# Sheet1.net
KiCad netlist of a schematic drawn in Altium Designer
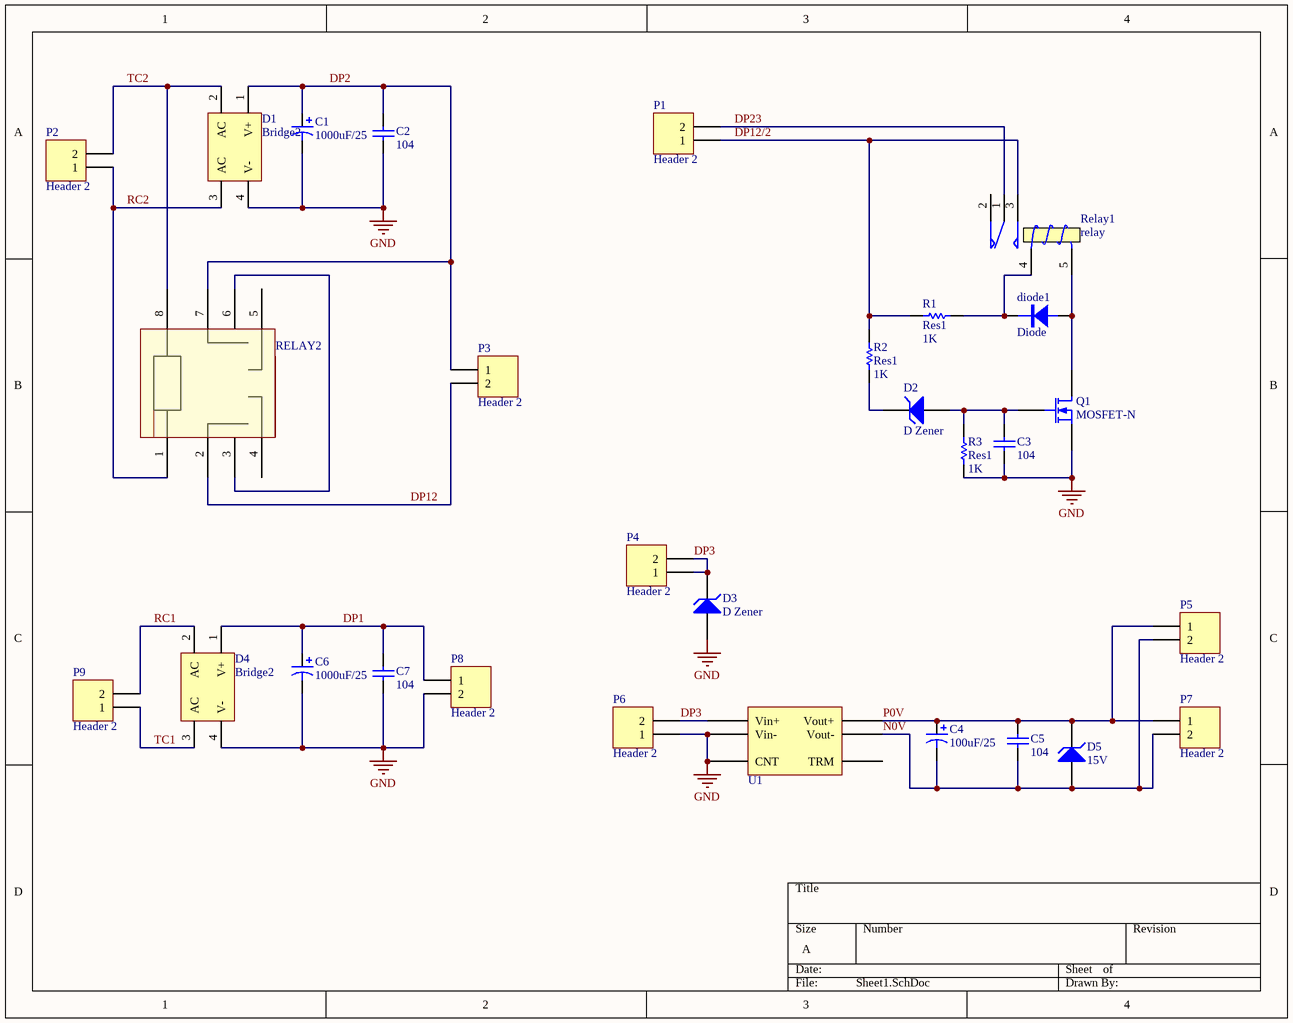
[diagram p0: Sheet1.SchDoc]

(export (version "E")
  (design (tool "Eeschema 10.0.6"))
  (components
    (comp (ref "C1")
      (value "1000uF/25")
      (footprint "RB7.6-15")
      (description "Polarized Capacitor (Radial)")
      (fields (field (name "PUBLISHER") "Altium Limited"))
      (libsource (lib "Miscellaneous Devices") (part "Cap Pol1"))
    )
    (comp (ref "C2")
      (value "104")
      (footprint "CN1.5")
      (description "Capacitor")
      (fields (field (name "PUBLISHER") "Altium Limited"))
      (libsource (lib "Miscellaneous Devices") (part "Cap"))
    )
    (comp (ref "C3")
      (value "104")
      (footprint "CN1.5")
      (description "Capacitor")
      (fields (field (name "PUBLISHER") "Altium Limited"))
      (libsource (lib "Miscellaneous Devices") (part "Cap"))
    )
    (comp (ref "C4")
      (value "100uF/25")
      (footprint "CP1.5/2.5")
      (description "Polarized Capacitor (Radial)")
      (fields (field (name "PUBLISHER") "Altium Limited"))
      (libsource (lib "Miscellaneous Devices") (part "Cap Pol1"))
    )
    (comp (ref "C5")
      (value "104")
      (footprint "CN1.5")
      (description "Capacitor")
      (fields (field (name "PUBLISHER") "Altium Limited"))
      (libsource (lib "Miscellaneous Devices") (part "Cap"))
    )
    (comp (ref "C6")
      (value "1000uF/25")
      (footprint "RB7.6-15")
      (description "Polarized Capacitor (Radial)")
      (fields (field (name "PUBLISHER") "Altium Limited"))
      (libsource (lib "Miscellaneous Devices") (part "Cap Pol1"))
    )
    (comp (ref "C7")
      (value "104")
      (footprint "CN1.5")
      (description "Capacitor")
      (fields (field (name "PUBLISHER") "Altium Limited"))
      (libsource (lib "Miscellaneous Devices") (part "Cap"))
    )
    (comp (ref "D1")
      (value "Bridge2")
      (footprint "KBU1010")
      (description "Diode Bridge")
      (fields (field (name "PUBLISHER") "Altium Limited"))
      (libsource (lib "Miscellaneous Devices") (part "Bridge2"))
    )
    (comp (ref "D2")
      (value "D Zener")
      (footprint "DZ1A")
      (description "Zener Diode")
      (fields (field (name "PUBLISHER") "Altium Limited"))
      (libsource (lib "Miscellaneous Devices") (part "D Zener"))
    )
    (comp (ref "D3")
      (value "D Zener")
      (footprint "DZ1A")
      (description "Zener Diode")
      (fields (field (name "PUBLISHER") "Altium Limited"))
      (libsource (lib "Miscellaneous Devices") (part "D Zener"))
    )
    (comp (ref "D4")
      (value "Bridge2")
      (footprint "KBP206")
      (description "Diode Bridge")
      (fields (field (name "PUBLISHER") "Altium Limited"))
      (libsource (lib "Miscellaneous Devices") (part "Bridge2"))
    )
    (comp (ref "D5")
      (value "15V")
      (footprint "DZ1A")
      (description "Zener Diode")
      (fields (field (name "PUBLISHER") "Altium Limited"))
      (libsource (lib "Miscellaneous Devices") (part "D Zener"))
    )
    (comp (ref "diode1")
      (value "Diode")
      (footprint "Diode s")
      (libsource (lib "dung_maker_2018") (part "Diode"))
    )
    (comp (ref "P1")
      (value "Header 2")
      (footprint "CON2 5.08")
      (description "Header, 2-Pin")
      (fields (field (name "PUBLISHER") "Altium Limited"))
      (libsource (lib "Miscellaneous Connectors") (part "Header 2"))
    )
    (comp (ref "P2")
      (value "Header 2")
      (footprint "CON2 5.08")
      (description "Header, 2-Pin")
      (fields (field (name "PUBLISHER") "Altium Limited"))
      (libsource (lib "Miscellaneous Connectors") (part "Header 2"))
    )
    (comp (ref "P3")
      (value "Header 2")
      (footprint "CON2 5.08")
      (description "Header, 2-Pin")
      (fields (field (name "PUBLISHER") "Altium Limited"))
      (libsource (lib "") (part "Header 2_1"))
    )
    (comp (ref "P4")
      (value "Header 2")
      (footprint "CON2 5.08")
      (description "Header, 2-Pin")
      (fields (field (name "PUBLISHER") "Altium Limited"))
      (libsource (lib "Miscellaneous Connectors") (part "Header 2"))
    )
    (comp (ref "P5")
      (value "Header 2")
      (footprint "CON2 5.08")
      (description "Header, 2-Pin")
      (fields (field (name "PUBLISHER") "Altium Limited"))
      (libsource (lib "") (part "Header 2_1"))
    )
    (comp (ref "P6")
      (value "Header 2")
      (footprint "CON2 5.08")
      (description "Header, 2-Pin")
      (fields (field (name "PUBLISHER") "Altium Limited"))
      (libsource (lib "Miscellaneous Connectors") (part "Header 2"))
    )
    (comp (ref "P7")
      (value "Header 2")
      (footprint "CON2 5.08")
      (description "Header, 2-Pin")
      (fields (field (name "PUBLISHER") "Altium Limited"))
      (libsource (lib "") (part "Header 2_1"))
    )
    (comp (ref "P8")
      (value "Header 2")
      (footprint "CON2 5.08")
      (description "Header, 2-Pin")
      (fields (field (name "PUBLISHER") "Altium Limited"))
      (libsource (lib "") (part "Header 2_1"))
    )
    (comp (ref "P9")
      (value "Header 2")
      (footprint "CON2 5.08")
      (description "Header, 2-Pin")
      (fields (field (name "PUBLISHER") "Altium Limited"))
      (libsource (lib "Miscellaneous Connectors") (part "Header 2"))
    )
    (comp (ref "Q1")
      (value "MOSFET-N")
      (footprint "Mosfet")
      (description "N-Channel MOSFET")
      (fields (field (name "PUBLISHER") "Altium Limited"))
      (libsource (lib "Miscellaneous Devices") (part "MOSFET-N"))
    )
    (comp (ref "R1")
      (value "Res1")
      (footprint "AXIAL-0.3")
      (description "Resistor")
      (fields (field (name "ALTIUM_VALUE") "1K") (field (name "PUBLISHER") "Altium Limited"))
      (libsource (lib "Miscellaneous Devices") (part "Res1"))
    )
    (comp (ref "R2")
      (value "Res1")
      (footprint "AXIAL-0.3")
      (description "Resistor")
      (fields (field (name "ALTIUM_VALUE") "1K") (field (name "PUBLISHER") "Altium Limited"))
      (libsource (lib "Miscellaneous Devices") (part "Res1"))
    )
    (comp (ref "R3")
      (value "Res1")
      (footprint "AXIAL-0.3")
      (description "Resistor")
      (fields (field (name "ALTIUM_VALUE") "1K") (field (name "PUBLISHER") "Altium Limited"))
      (libsource (lib "Miscellaneous Devices") (part "Res1"))
    )
    (comp (ref "Relay1")
      (value "relay")
      (footprint "Relay1")
      (description "SPDT Relay")
      (fields (field (name "PUBLISHER") "Altium Limited"))
      (libsource (lib "dung_maker_2018") (part "Relay"))
    )
    (comp (ref "RELAY2")
      (value "RY12W-K")
      (footprint "RY-Series")
      (libsource (lib "dung_maker_2018") (part "RY12W-K"))
    )
    (comp (ref "U1") (value "PP15") (footprint "PP15") (libsource (lib "dung_maker_2018") (part "PP15")))
  )
  (nets
    (net (code "1") (name "/DP1") (class "Default")
      (node (ref "C6") (pin "1") (pinfunction "1_1") (pintype "passive"))
      (node (ref "C7") (pin "2") (pinfunction "2_2") (pintype "passive"))
      (node (ref "D4") (pin "1") (pinfunction "V+_1") (pintype "passive"))
      (node (ref "P8") (pin "1") (pinfunction "1_1") (pintype "passive"))
    )
    (net (code "2") (name "/DP2") (class "Default")
      (node (ref "C1") (pin "1") (pinfunction "1_1") (pintype "passive"))
      (node (ref "C2") (pin "2") (pinfunction "2_2") (pintype "passive"))
      (node (ref "D1") (pin "1") (pinfunction "V+_1") (pintype "passive"))
      (node (ref "P3") (pin "1") (pinfunction "1_1") (pintype "passive"))
      (node (ref "RELAY2") (pin "7") (pinfunction "7_7") (pintype "passive"))
    )
    (net (code "3") (name "/DP3") (class "Default")
      (node (ref "D3") (pin "2") (pinfunction "K_2") (pintype "passive"))
      (node (ref "P4") (pin "1") (pinfunction "1_1") (pintype "passive"))
      (node (ref "P4") (pin "2") (pinfunction "2_2") (pintype "passive"))
      (node (ref "P6") (pin "2") (pinfunction "2_2") (pintype "passive"))
      (node (ref "U1") (pin "1") (pinfunction "Vin+_1") (pintype "passive"))
    )
    (net (code "4") (name "/DP12") (class "Default")
      (node (ref "P3") (pin "2") (pinfunction "2_2") (pintype "passive"))
      (node (ref "RELAY2") (pin "2") (pinfunction "2_2") (pintype "passive"))
    )
    (net (code "5") (name "/DP12{slash}2") (class "Default")
      (node (ref "P1") (pin "1") (pinfunction "1_1") (pintype "passive"))
      (node (ref "R1") (pin "1") (pinfunction "1_1") (pintype "passive"))
      (node (ref "R2") (pin "2") (pinfunction "2_2") (pintype "passive"))
      (node (ref "Relay1") (pin "3") (pinfunction "NO_3") (pintype "passive"))
    )
    (net (code "6") (name "/DP23") (class "Default")
      (node (ref "P1") (pin "2") (pinfunction "2_2") (pintype "passive"))
      (node (ref "Relay1") (pin "1") (pinfunction "COM_1") (pintype "passive"))
    )
    (net (code "7") (name "/N0V") (class "Default")
      (node (ref "C4") (pin "2") (pinfunction "2_2") (pintype "passive"))
      (node (ref "C5") (pin "1") (pinfunction "1_1") (pintype "passive"))
      (node (ref "D5") (pin "1") (pinfunction "A_1") (pintype "passive"))
      (node (ref "P5") (pin "2") (pinfunction "2_2") (pintype "passive"))
      (node (ref "P7") (pin "2") (pinfunction "2_2") (pintype "passive"))
      (node (ref "U1") (pin "5") (pinfunction "Vout-_5") (pintype "passive"))
    )
    (net (code "8") (name "/P0V") (class "Default")
      (node (ref "C4") (pin "1") (pinfunction "1_1") (pintype "passive"))
      (node (ref "C5") (pin "2") (pinfunction "2_2") (pintype "passive"))
      (node (ref "D5") (pin "2") (pinfunction "K_2") (pintype "passive"))
      (node (ref "P5") (pin "1") (pinfunction "1_1") (pintype "passive"))
      (node (ref "P7") (pin "1") (pinfunction "1_1") (pintype "passive"))
      (node (ref "U1") (pin "4") (pinfunction "Vout+_4") (pintype "passive"))
    )
    (net (code "9") (name "/RC1") (class "Default")
      (node (ref "D4") (pin "2") (pinfunction "AC_2") (pintype "passive"))
      (node (ref "P9") (pin "2") (pinfunction "2_2") (pintype "passive"))
    )
    (net (code "10") (name "/RC2") (class "Default")
      (node (ref "D1") (pin "3") (pinfunction "AC_3") (pintype "passive"))
      (node (ref "P2") (pin "1") (pinfunction "1_1") (pintype "passive"))
      (node (ref "RELAY2") (pin "1") (pinfunction "1_1") (pintype "passive"))
    )
    (net (code "11") (name "/TC1") (class "Default")
      (node (ref "D4") (pin "3") (pinfunction "AC_3") (pintype "passive"))
      (node (ref "P9") (pin "1") (pinfunction "1_1") (pintype "passive"))
    )
    (net (code "12") (name "/TC2") (class "Default")
      (node (ref "D1") (pin "2") (pinfunction "AC_2") (pintype "passive"))
      (node (ref "P2") (pin "2") (pinfunction "2_2") (pintype "passive"))
      (node (ref "RELAY2") (pin "8") (pinfunction "8_8") (pintype "passive"))
    )
    (net (code "13") (name "GND") (class "Default")
      (node (ref "C1") (pin "2") (pinfunction "2_2") (pintype "passive"))
      (node (ref "C2") (pin "1") (pinfunction "1_1") (pintype "passive"))
      (node (ref "C3") (pin "1") (pinfunction "1_1") (pintype "passive"))
      (node (ref "C6") (pin "2") (pinfunction "2_2") (pintype "passive"))
      (node (ref "C7") (pin "1") (pinfunction "1_1") (pintype "passive"))
      (node (ref "D1") (pin "4") (pinfunction "V-_4") (pintype "passive"))
      (node (ref "D3") (pin "1") (pinfunction "A_1") (pintype "passive"))
      (node (ref "D4") (pin "4") (pinfunction "V-_4") (pintype "passive"))
      (node (ref "P6") (pin "1") (pinfunction "1_1") (pintype "passive"))
      (node (ref "P8") (pin "2") (pinfunction "2_2") (pintype "passive"))
      (node (ref "Q1") (pin "3") (pinfunction "S_3") (pintype "passive"))
      (node (ref "R3") (pin "1") (pinfunction "1_1") (pintype "passive"))
      (node (ref "U1") (pin "2") (pinfunction "Vin-_2") (pintype "passive"))
      (node (ref "U1") (pin "3") (pinfunction "CNT_3") (pintype "passive"))
    )
    (net (code "14") (name "Net-(D2-A)") (class "Default")
      (node (ref "C3") (pin "2") (pinfunction "2_2") (pintype "passive"))
      (node (ref "D2") (pin "1") (pinfunction "A_1") (pintype "passive"))
      (node (ref "Q1") (pin "2") (pinfunction "G_2") (pintype "passive"))
      (node (ref "R3") (pin "2") (pinfunction "2_2") (pintype "passive"))
    )
    (net (code "15") (name "Net-(D2-K)") (class "Default")
      (node (ref "D2") (pin "2") (pinfunction "K_2") (pintype "passive"))
      (node (ref "R2") (pin "1") (pinfunction "1_1") (pintype "passive"))
    )
    (net (code "16") (name "Net-(Q1-D)") (class "Default")
      (node (ref "Q1") (pin "1") (pinfunction "D_1") (pintype "passive"))
      (node (ref "Relay1") (pin "5") (pinfunction "T2_5") (pintype "passive"))
      (node (ref "diode1") (pin "1") (pinfunction "1_1") (pintype "passive"))
    )
    (net (code "17") (name "Net-(RELAY2-Pad3)") (class "Default")
      (node (ref "RELAY2") (pin "3") (pinfunction "3_3") (pintype "passive"))
      (node (ref "RELAY2") (pin "6") (pinfunction "6_6") (pintype "passive"))
    )
    (net (code "18") (name "Net-(Relay1-T1)") (class "Default")
      (node (ref "R1") (pin "2") (pinfunction "2_2") (pintype "passive"))
      (node (ref "Relay1") (pin "4") (pinfunction "T1_4") (pintype "passive"))
      (node (ref "diode1") (pin "2") (pinfunction "2_2") (pintype "passive"))
    )
    (net (code "19") (name "unconnected-(RELAY2-Pad4)") (class "Default")
      (node (ref "RELAY2") (pin "4") (pinfunction "4_4") (pintype "passive"))
    )
    (net (code "20") (name "unconnected-(RELAY2-Pad5)") (class "Default")
      (node (ref "RELAY2") (pin "5") (pinfunction "5_5") (pintype "passive"))
    )
    (net (code "21") (name "unconnected-(Relay1-NC-Pad2)") (class "Default")
      (node (ref "Relay1") (pin "2") (pinfunction "NC_2") (pintype "passive"))
    )
    (net (code "22") (name "unconnected-(U1-TRM-Pad6)") (class "Default")
      (node (ref "U1") (pin "6") (pinfunction "TRM_6") (pintype "passive"))
    )
  )
)
